# 6pin_break_out.net
KiCad netlist of a schematic drawn in EAGLE
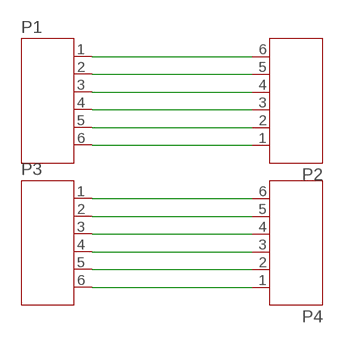
[diagram p0: schematic, sheet 1]

(export (version "E")
  (design (tool "Eeschema 10.0.6"))
  (components
    (comp (ref "P1")
      (value "JST-PH6")
      (footprint "eagle-import:JST-PH6")
      (libsource (lib "eagle-import") (part "JST-PH6"))
    )
    (comp (ref "P2")
      (value "JST-PH6")
      (footprint "eagle-import:JST-PH6")
      (libsource (lib "eagle-import") (part "JST-PH6"))
    )
    (comp (ref "P3")
      (value "JST-PH6")
      (footprint "eagle-import:JST-PH6")
      (libsource (lib "eagle-import") (part "JST-PH6"))
    )
    (comp (ref "P4")
      (value "JST-PH6")
      (footprint "eagle-import:JST-PH6")
      (libsource (lib "eagle-import") (part "JST-PH6"))
    )
  )
  (nets
    (net (code "1") (name "Net-(P1-Pad1)") (class "Default")
      (node (ref "P1") (pin "1") (pinfunction "1_1") (pintype "passive"))
      (node (ref "P2") (pin "6") (pinfunction "6_6") (pintype "passive"))
    )
    (net (code "2") (name "Net-(P1-Pad2)") (class "Default")
      (node (ref "P1") (pin "2") (pinfunction "2_2") (pintype "passive"))
      (node (ref "P2") (pin "5") (pinfunction "5_5") (pintype "passive"))
    )
    (net (code "3") (name "Net-(P1-Pad3)") (class "Default")
      (node (ref "P1") (pin "3") (pinfunction "3_3") (pintype "passive"))
      (node (ref "P2") (pin "4") (pinfunction "4_4") (pintype "passive"))
    )
    (net (code "4") (name "Net-(P1-Pad4)") (class "Default")
      (node (ref "P1") (pin "4") (pinfunction "4_4") (pintype "passive"))
      (node (ref "P2") (pin "3") (pinfunction "3_3") (pintype "passive"))
    )
    (net (code "5") (name "Net-(P1-Pad5)") (class "Default")
      (node (ref "P1") (pin "5") (pinfunction "5_5") (pintype "passive"))
      (node (ref "P2") (pin "2") (pinfunction "2_2") (pintype "passive"))
    )
    (net (code "6") (name "Net-(P1-Pad6)") (class "Default")
      (node (ref "P1") (pin "6") (pinfunction "6_6") (pintype "passive"))
      (node (ref "P2") (pin "1") (pinfunction "1_1") (pintype "passive"))
    )
    (net (code "7") (name "Net-(P3-Pad1)") (class "Default")
      (node (ref "P3") (pin "1") (pinfunction "1_1") (pintype "passive"))
      (node (ref "P4") (pin "6") (pinfunction "6_6") (pintype "passive"))
    )
    (net (code "8") (name "Net-(P3-Pad2)") (class "Default")
      (node (ref "P3") (pin "2") (pinfunction "2_2") (pintype "passive"))
      (node (ref "P4") (pin "5") (pinfunction "5_5") (pintype "passive"))
    )
    (net (code "9") (name "Net-(P3-Pad3)") (class "Default")
      (node (ref "P3") (pin "3") (pinfunction "3_3") (pintype "passive"))
      (node (ref "P4") (pin "4") (pinfunction "4_4") (pintype "passive"))
    )
    (net (code "10") (name "Net-(P3-Pad4)") (class "Default")
      (node (ref "P3") (pin "4") (pinfunction "4_4") (pintype "passive"))
      (node (ref "P4") (pin "3") (pinfunction "3_3") (pintype "passive"))
    )
    (net (code "11") (name "Net-(P3-Pad5)") (class "Default")
      (node (ref "P3") (pin "5") (pinfunction "5_5") (pintype "passive"))
      (node (ref "P4") (pin "2") (pinfunction "2_2") (pintype "passive"))
    )
    (net (code "12") (name "Net-(P3-Pad6)") (class "Default")
      (node (ref "P3") (pin "6") (pinfunction "6_6") (pintype "passive"))
      (node (ref "P4") (pin "1") (pinfunction "1_1") (pintype "passive"))
    )
  )
)
